# PCB_111000_CA.net
KiCad netlist of a schematic drawn in EAGLE
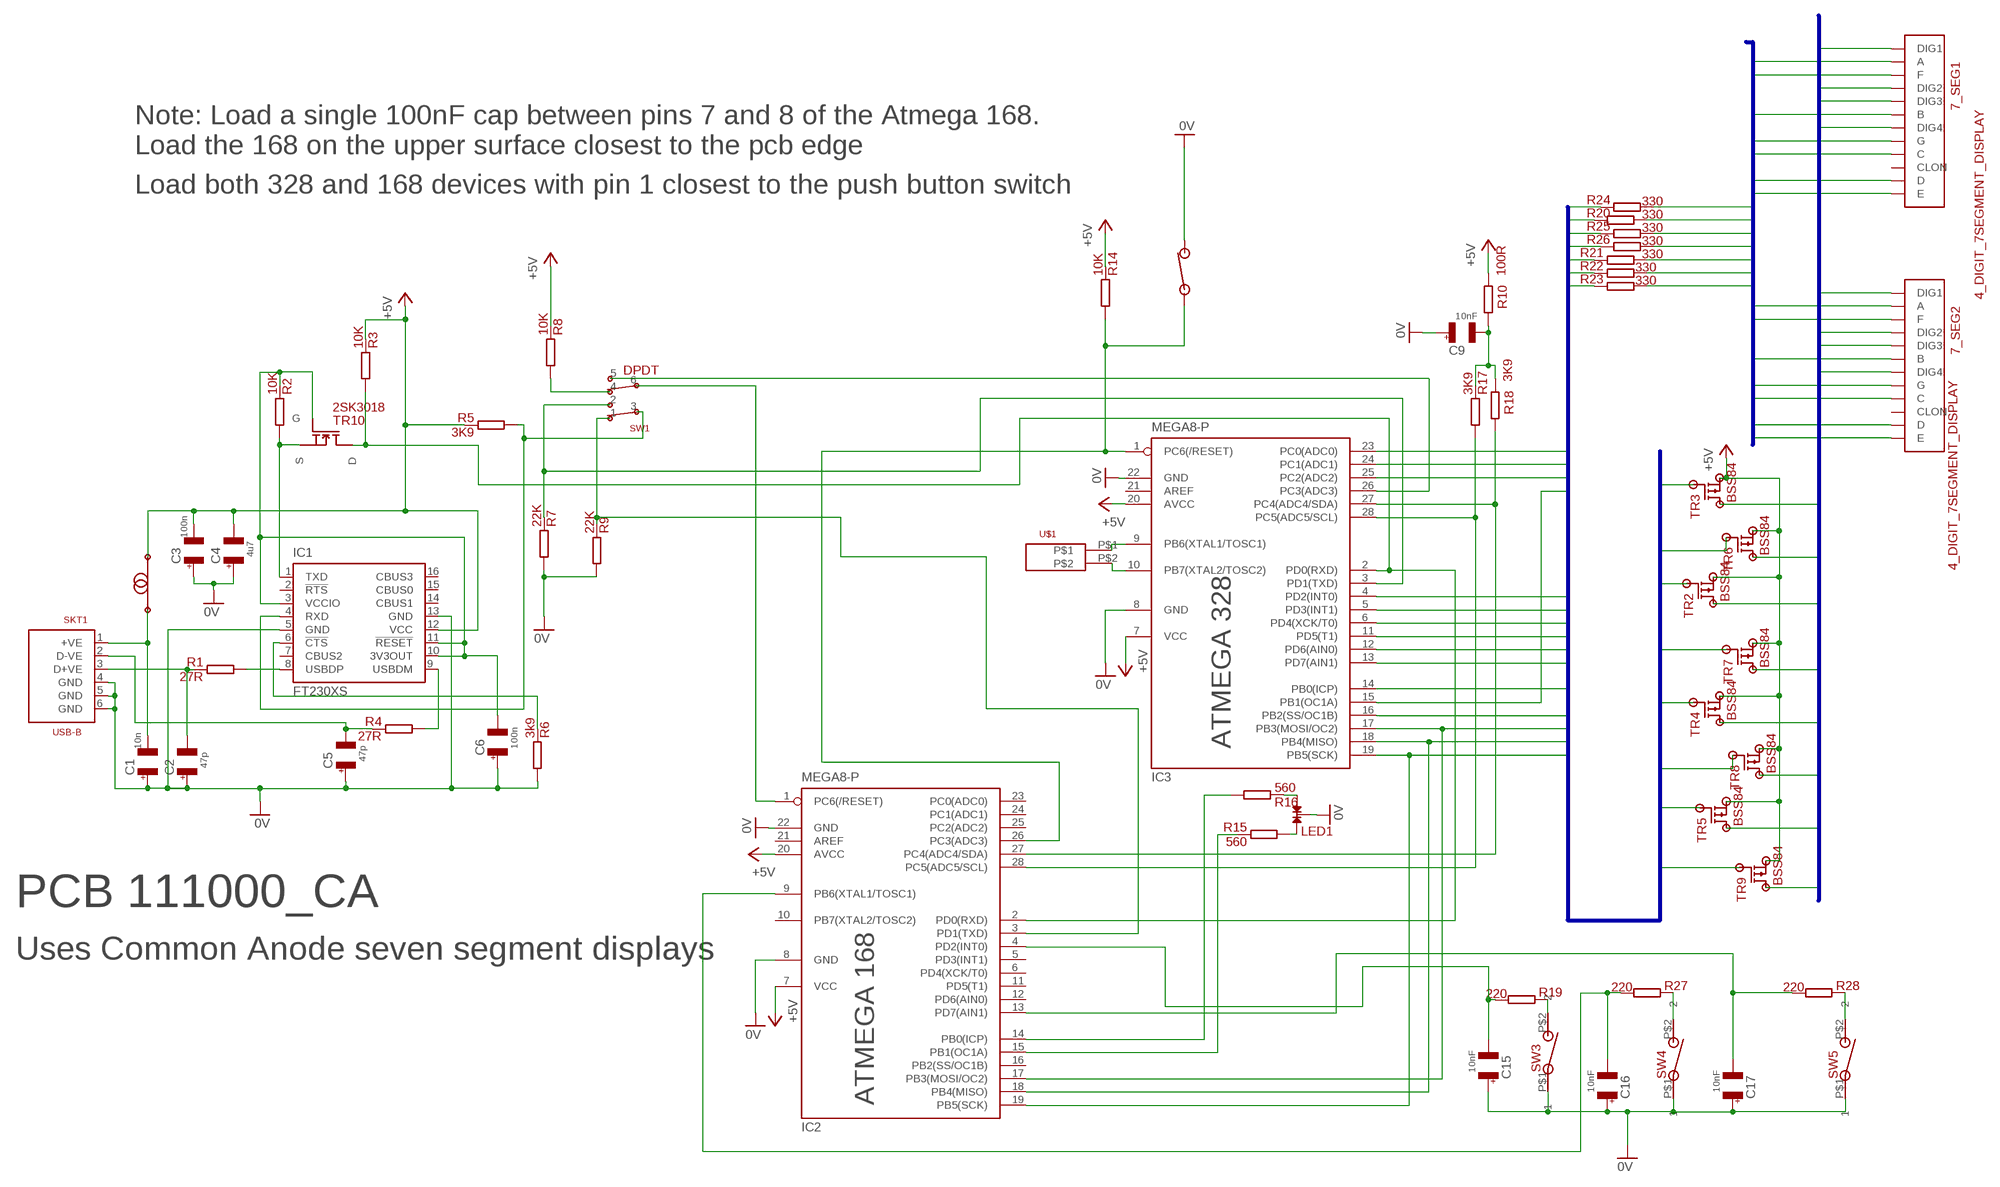
[diagram p0: schematic, sheet 1]

(export (version "E")
  (design (tool "Eeschema 10.0.6"))
  (components
    (comp (ref "7_SEG1")
      (value "4_DIGIT_7SEGMENT_DISPLAY")
      (footprint "eagle-import:4_DIGIT_7SEGMENT_DISPLAY")
      (libsource (lib "eagle-import") (part "4_DIGIT_7SEGMENT_DISPLAY"))
    )
    (comp (ref "7_SEG2")
      (value "4_DIGIT_7SEGMENT_DISPLAY")
      (footprint "eagle-import:4_DIGIT_7SEGMENT_DISPLAY")
      (libsource (lib "eagle-import") (part "4_DIGIT_7SEGMENT_DISPLAY"))
    )
    (comp (ref "C1")
      (value "10n")
      (footprint "eagle-import:1206")
      (libsource (lib "eagle-import") (part "1206C"))
    )
    (comp (ref "C2")
      (value "47p")
      (footprint "eagle-import:1206")
      (libsource (lib "eagle-import") (part "1206C"))
    )
    (comp (ref "C3")
      (value "100n")
      (footprint "eagle-import:1206")
      (libsource (lib "eagle-import") (part "1206C"))
    )
    (comp (ref "C4")
      (value "4u7")
      (footprint "eagle-import:1206")
      (libsource (lib "eagle-import") (part "1206C"))
    )
    (comp (ref "C5")
      (value "47p")
      (footprint "eagle-import:1206")
      (libsource (lib "eagle-import") (part "1206C"))
    )
    (comp (ref "C6")
      (value "100n")
      (footprint "eagle-import:1206")
      (libsource (lib "eagle-import") (part "1206C"))
    )
    (comp (ref "C9")
      (value "10nF")
      (footprint "eagle-import:1206")
      (libsource (lib "eagle-import") (part "1206C"))
    )
    (comp (ref "C15")
      (value "10nF")
      (footprint "eagle-import:1206")
      (libsource (lib "eagle-import") (part "1206C"))
    )
    (comp (ref "C16")
      (value "10nF")
      (footprint "eagle-import:1206")
      (libsource (lib "eagle-import") (part "1206C"))
    )
    (comp (ref "C17")
      (value "10nF")
      (footprint "eagle-import:1206")
      (libsource (lib "eagle-import") (part "1206C"))
    )
    (comp (ref "IC1")
      (value "FT230XS")
      (footprint "eagle-import:SSOP16")
      (libsource (lib "eagle-import") (part "FT230XS"))
    )
    (comp (ref "IC2")
      (value "MEGA8-P")
      (footprint "eagle-import:DIL28-3")
      (libsource (lib "eagle-import") (part "MEGA8-P"))
    )
    (comp (ref "IC3")
      (value "MEGA8-P")
      (footprint "eagle-import:DIL28-3")
      (libsource (lib "eagle-import") (part "MEGA8-P"))
    )
    (comp (ref "L1")
      (value "CHOKE")
      (footprint "eagle-import:1206")
      (libsource (lib "eagle-import") (part "CHOKE"))
    )
    (comp (ref "LED1")
      (value "LED")
      (footprint "eagle-import:CA_DUAL_LED")
      (libsource (lib "eagle-import") (part "LED"))
    )
    (comp (ref "R1")
      (value "27R")
      (footprint "eagle-import:1206")
      (libsource (lib "eagle-import") (part "1206R"))
    )
    (comp (ref "R2")
      (value "10K")
      (footprint "eagle-import:1206")
      (libsource (lib "eagle-import") (part "1206R"))
    )
    (comp (ref "R3")
      (value "10K")
      (footprint "eagle-import:1206")
      (libsource (lib "eagle-import") (part "1206R"))
    )
    (comp (ref "R4")
      (value "27R")
      (footprint "eagle-import:1206")
      (libsource (lib "eagle-import") (part "1206R"))
    )
    (comp (ref "R5")
      (value "3K9")
      (footprint "eagle-import:1206")
      (libsource (lib "eagle-import") (part "1206R"))
    )
    (comp (ref "R6")
      (value "3k9")
      (footprint "eagle-import:1206")
      (libsource (lib "eagle-import") (part "1206R"))
    )
    (comp (ref "R7")
      (value "22K")
      (footprint "eagle-import:1206")
      (libsource (lib "eagle-import") (part "1206R"))
    )
    (comp (ref "R8")
      (value "10K")
      (footprint "eagle-import:1206")
      (libsource (lib "eagle-import") (part "1206R"))
    )
    (comp (ref "R9")
      (value "22K")
      (footprint "eagle-import:1206")
      (libsource (lib "eagle-import") (part "1206R"))
    )
    (comp (ref "R10")
      (value "100R")
      (footprint "eagle-import:1206")
      (libsource (lib "eagle-import") (part "1206R"))
    )
    (comp (ref "R14")
      (value "10K")
      (footprint "eagle-import:1206")
      (libsource (lib "eagle-import") (part "1206R"))
    )
    (comp (ref "R15")
      (value "560")
      (footprint "eagle-import:1206")
      (libsource (lib "eagle-import") (part "1206R"))
    )
    (comp (ref "R16")
      (value "560")
      (footprint "eagle-import:1206")
      (libsource (lib "eagle-import") (part "1206R"))
    )
    (comp (ref "R17")
      (value "3K9")
      (footprint "eagle-import:1206")
      (libsource (lib "eagle-import") (part "1206R"))
    )
    (comp (ref "R18")
      (value "3K9")
      (footprint "eagle-import:1206")
      (libsource (lib "eagle-import") (part "1206R"))
    )
    (comp (ref "R19")
      (value "220")
      (footprint "eagle-import:1206")
      (libsource (lib "eagle-import") (part "1206R"))
    )
    (comp (ref "R20")
      (value "330")
      (footprint "eagle-import:1206")
      (libsource (lib "eagle-import") (part "1206R"))
    )
    (comp (ref "R21")
      (value "330")
      (footprint "eagle-import:1206")
      (libsource (lib "eagle-import") (part "1206R"))
    )
    (comp (ref "R22")
      (value "330")
      (footprint "eagle-import:1206")
      (libsource (lib "eagle-import") (part "1206R"))
    )
    (comp (ref "R23")
      (value "330")
      (footprint "eagle-import:1206")
      (libsource (lib "eagle-import") (part "1206R"))
    )
    (comp (ref "R24")
      (value "330")
      (footprint "eagle-import:1206")
      (libsource (lib "eagle-import") (part "1206R"))
    )
    (comp (ref "R25")
      (value "330")
      (footprint "eagle-import:1206")
      (libsource (lib "eagle-import") (part "1206R"))
    )
    (comp (ref "R26")
      (value "330")
      (footprint "eagle-import:1206")
      (libsource (lib "eagle-import") (part "1206R"))
    )
    (comp (ref "R27")
      (value "220")
      (footprint "eagle-import:1206")
      (libsource (lib "eagle-import") (part "1206R"))
    )
    (comp (ref "R28")
      (value "220")
      (footprint "eagle-import:1206")
      (libsource (lib "eagle-import") (part "1206R"))
    )
    (comp (ref "SKT1")
      (value "USB-B")
      (footprint "eagle-import:USB-B")
      (libsource (lib "eagle-import") (part "USB-B"))
    )
    (comp (ref "SW1")
      (value "DPDT")
      (footprint "eagle-import:DPDT_SWITCH")
      (libsource (lib "eagle-import") (part "DPDT"))
    )
    (comp (ref "SW2")
      (value "NO_SW")
      (footprint "eagle-import:SM_NO_PUSH_BUTTON")
      (libsource (lib "eagle-import") (part "NO_SW"))
    )
    (comp (ref "SW3")
      (value "NO_PB_1")
      (footprint "eagle-import:RE51-0711")
      (libsource (lib "eagle-import") (part "NO_PB_1"))
    )
    (comp (ref "SW4")
      (value "NO_PB_1")
      (footprint "eagle-import:RE51-0711")
      (libsource (lib "eagle-import") (part "NO_PB_1"))
    )
    (comp (ref "SW5")
      (value "NO_PB_1")
      (footprint "eagle-import:RE51-0711")
      (libsource (lib "eagle-import") (part "NO_PB_1"))
    )
    (comp (ref "TR2")
      (value "BSS84")
      (footprint "eagle-import:SOT23")
      (libsource (lib "eagle-import") (part "BSS84"))
    )
    (comp (ref "TR3")
      (value "BSS84")
      (footprint "eagle-import:SOT23")
      (libsource (lib "eagle-import") (part "BSS84"))
    )
    (comp (ref "TR4")
      (value "BSS84")
      (footprint "eagle-import:SOT23")
      (libsource (lib "eagle-import") (part "BSS84"))
    )
    (comp (ref "TR5")
      (value "BSS84")
      (footprint "eagle-import:SOT23")
      (libsource (lib "eagle-import") (part "BSS84"))
    )
    (comp (ref "TR6")
      (value "BSS84")
      (footprint "eagle-import:SOT23")
      (libsource (lib "eagle-import") (part "BSS84"))
    )
    (comp (ref "TR7")
      (value "BSS84")
      (footprint "eagle-import:SOT23")
      (libsource (lib "eagle-import") (part "BSS84"))
    )
    (comp (ref "TR8")
      (value "BSS84")
      (footprint "eagle-import:SOT23")
      (libsource (lib "eagle-import") (part "BSS84"))
    )
    (comp (ref "TR9")
      (value "BSS84")
      (footprint "eagle-import:SOT23")
      (libsource (lib "eagle-import") (part "BSS84"))
    )
    (comp (ref "TR10")
      (value "2SK3018")
      (footprint "eagle-import:2SK3018")
      (libsource (lib "eagle-import") (part "2SK3018"))
    )
    (comp (ref "U$1")
      (value "XTAL")
      (footprint "eagle-import:XTAL_VIAS")
      (libsource (lib "eagle-import") (part "XTAL"))
    )
  )
  (nets
    (net (code "1") (name "+5V") (class "Default")
      (node (ref "C3") (pin "P$2") (pinfunction "2_P$2") (pintype "bidirectional"))
      (node (ref "C4") (pin "P$2") (pinfunction "2_P$2") (pintype "bidirectional"))
      (node (ref "IC1") (pin "12") (pinfunction "VCC_12") (pintype "power_in"))
      (node (ref "IC2") (pin "20") (pinfunction "AVCC_20") (pintype "power_in"))
      (node (ref "IC2") (pin "7") (pinfunction "VCC_7") (pintype "power_in"))
      (node (ref "IC3") (pin "20") (pinfunction "AVCC_20") (pintype "power_in"))
      (node (ref "IC3") (pin "7") (pinfunction "VCC_7") (pintype "power_in"))
      (node (ref "L1") (pin "P$2") (pinfunction "2_P$2") (pintype "bidirectional"))
      (node (ref "R10") (pin "P$2") (pinfunction "P$2_P$2") (pintype "bidirectional"))
      (node (ref "R14") (pin "P$2") (pinfunction "P$2_P$2") (pintype "bidirectional"))
      (node (ref "R3") (pin "P$2") (pinfunction "P$2_P$2") (pintype "bidirectional"))
      (node (ref "R5") (pin "P$2") (pinfunction "P$2_P$2") (pintype "bidirectional"))
      (node (ref "R8") (pin "P$2") (pinfunction "P$2_P$2") (pintype "bidirectional"))
      (node (ref "TR2") (pin "2") (pinfunction "S_2") (pintype "bidirectional"))
      (node (ref "TR3") (pin "2") (pinfunction "S_2") (pintype "bidirectional"))
      (node (ref "TR4") (pin "2") (pinfunction "S_2") (pintype "bidirectional"))
      (node (ref "TR5") (pin "2") (pinfunction "S_2") (pintype "bidirectional"))
      (node (ref "TR6") (pin "2") (pinfunction "S_2") (pintype "bidirectional"))
      (node (ref "TR7") (pin "2") (pinfunction "S_2") (pintype "bidirectional"))
      (node (ref "TR8") (pin "2") (pinfunction "S_2") (pintype "bidirectional"))
      (node (ref "TR9") (pin "2") (pinfunction "S_2") (pintype "bidirectional"))
    )
    (net (code "2") (name "/DIGIT0") (class "Default")
      (node (ref "7_SEG1") (pin "P$12") (pinfunction "DIG1_P$12") (pintype "bidirectional"))
      (node (ref "TR4") (pin "3") (pinfunction "D_3") (pintype "bidirectional"))
    )
    (net (code "3") (name "/DIGIT1") (class "Default")
      (node (ref "7_SEG1") (pin "P$9") (pinfunction "DIG2_P$9") (pintype "bidirectional"))
      (node (ref "TR8") (pin "3") (pinfunction "D_3") (pintype "bidirectional"))
    )
    (net (code "4") (name "/DIGIT2") (class "Default")
      (node (ref "7_SEG1") (pin "P$8") (pinfunction "DIG3_P$8") (pintype "bidirectional"))
      (node (ref "TR5") (pin "3") (pinfunction "D_3") (pintype "bidirectional"))
    )
    (net (code "5") (name "/DIGIT3") (class "Default")
      (node (ref "7_SEG1") (pin "P$6") (pinfunction "DIG4_P$6") (pintype "bidirectional"))
      (node (ref "TR9") (pin "3") (pinfunction "D_3") (pintype "bidirectional"))
    )
    (net (code "6") (name "/DIGIT4") (class "Default")
      (node (ref "7_SEG2") (pin "P$12") (pinfunction "DIG1_P$12") (pintype "bidirectional"))
      (node (ref "TR3") (pin "3") (pinfunction "D_3") (pintype "bidirectional"))
    )
    (net (code "7") (name "/DIGIT5") (class "Default")
      (node (ref "7_SEG2") (pin "P$9") (pinfunction "DIG2_P$9") (pintype "bidirectional"))
      (node (ref "TR6") (pin "3") (pinfunction "D_3") (pintype "bidirectional"))
    )
    (net (code "8") (name "/DIGIT6") (class "Default")
      (node (ref "7_SEG2") (pin "P$8") (pinfunction "DIG3_P$8") (pintype "bidirectional"))
      (node (ref "TR2") (pin "3") (pinfunction "D_3") (pintype "bidirectional"))
    )
    (net (code "9") (name "/DIGIT7") (class "Default")
      (node (ref "7_SEG2") (pin "P$6") (pinfunction "DIG4_P$6") (pintype "bidirectional"))
      (node (ref "TR7") (pin "3") (pinfunction "D_3") (pintype "bidirectional"))
    )
    (net (code "10") (name "/DISPLAY_DRIVER0") (class "Default")
      (node (ref "IC3") (pin "15") (pinfunction "PB1(OC1A)_15") (pintype "bidirectional"))
      (node (ref "R24") (pin "P$2") (pinfunction "P$2_P$2") (pintype "bidirectional"))
    )
    (net (code "11") (name "/DISPLAY_DRIVER1") (class "Default")
      (node (ref "IC3") (pin "4") (pinfunction "PD2(INT0)_4") (pintype "bidirectional"))
      (node (ref "R20") (pin "P$2") (pinfunction "P$2_P$2") (pintype "bidirectional"))
    )
    (net (code "12") (name "/DISPLAY_DRIVER2") (class "Default")
      (node (ref "IC3") (pin "5") (pinfunction "PD3(INT1)_5") (pintype "bidirectional"))
      (node (ref "R25") (pin "P$2") (pinfunction "P$2_P$2") (pintype "bidirectional"))
    )
    (net (code "13") (name "/DISPLAY_DRIVER3") (class "Default")
      (node (ref "IC3") (pin "6") (pinfunction "PD4(XCK/T0)_6") (pintype "bidirectional"))
      (node (ref "R26") (pin "P$2") (pinfunction "P$2_P$2") (pintype "bidirectional"))
    )
    (net (code "14") (name "/DISPLAY_DRIVER4") (class "Default")
      (node (ref "IC3") (pin "11") (pinfunction "PD5(T1)_11") (pintype "bidirectional"))
      (node (ref "R21") (pin "P$2") (pinfunction "P$2_P$2") (pintype "bidirectional"))
    )
    (net (code "15") (name "/DISPLAY_DRIVER5") (class "Default")
      (node (ref "IC3") (pin "12") (pinfunction "PD6(AIN0)_12") (pintype "bidirectional"))
      (node (ref "R22") (pin "P$2") (pinfunction "P$2_P$2") (pintype "bidirectional"))
    )
    (net (code "16") (name "/DISPLAY_DRIVER6") (class "Default")
      (node (ref "IC3") (pin "13") (pinfunction "PD7(AIN1)_13") (pintype "bidirectional"))
      (node (ref "R23") (pin "P$2") (pinfunction "P$2_P$2") (pintype "bidirectional"))
    )
    (net (code "17") (name "/DISPLAY_DRIVER8") (class "Default")
      (node (ref "IC3") (pin "14") (pinfunction "PB0(ICP)_14") (pintype "bidirectional"))
      (node (ref "TR3") (pin "1") (pinfunction "G_1") (pintype "bidirectional"))
    )
    (net (code "18") (name "/DISPLAY_DRIVER9") (class "Default")
      (node (ref "IC3") (pin "16") (pinfunction "PB2(SS/OC1B)_16") (pintype "bidirectional"))
      (node (ref "TR6") (pin "1") (pinfunction "G_1") (pintype "bidirectional"))
    )
    (net (code "19") (name "/DISPLAY_DRIVER10") (class "Default")
      (node (ref "IC2") (pin "17") (pinfunction "PB3(MOSI/OC2)_17") (pintype "bidirectional"))
      (node (ref "IC3") (pin "17") (pinfunction "PB3(MOSI/OC2)_17") (pintype "bidirectional"))
      (node (ref "TR2") (pin "1") (pinfunction "G_1") (pintype "bidirectional"))
    )
    (net (code "20") (name "/DISPLAY_DRIVER11") (class "Default")
      (node (ref "IC2") (pin "18") (pinfunction "PB4(MISO)_18") (pintype "bidirectional"))
      (node (ref "IC3") (pin "18") (pinfunction "PB4(MISO)_18") (pintype "bidirectional"))
      (node (ref "TR7") (pin "1") (pinfunction "G_1") (pintype "bidirectional"))
    )
    (net (code "21") (name "/DISPLAY_DRIVER12") (class "Default")
      (node (ref "IC2") (pin "19") (pinfunction "PB5(SCK)_19") (pintype "bidirectional"))
      (node (ref "IC3") (pin "19") (pinfunction "PB5(SCK)_19") (pintype "bidirectional"))
      (node (ref "TR4") (pin "1") (pinfunction "G_1") (pintype "bidirectional"))
    )
    (net (code "22") (name "/DISPLAY_DRIVER13") (class "Default")
      (node (ref "IC3") (pin "23") (pinfunction "PC0(ADC0)_23") (pintype "bidirectional"))
      (node (ref "TR8") (pin "1") (pinfunction "G_1") (pintype "bidirectional"))
    )
    (net (code "23") (name "/DISPLAY_DRIVER14") (class "Default")
      (node (ref "IC3") (pin "24") (pinfunction "PC1(ADC1)_24") (pintype "bidirectional"))
      (node (ref "TR5") (pin "1") (pinfunction "G_1") (pintype "bidirectional"))
    )
    (net (code "24") (name "/DISPLAY_DRIVER15") (class "Default")
      (node (ref "IC3") (pin "25") (pinfunction "PC2(ADC2)_25") (pintype "bidirectional"))
      (node (ref "TR9") (pin "1") (pinfunction "G_1") (pintype "bidirectional"))
    )
    (net (code "25") (name "/SEVEN_SEG0") (class "Default")
      (node (ref "7_SEG1") (pin "P$11") (pinfunction "A_P$11") (pintype "bidirectional"))
      (node (ref "7_SEG2") (pin "P$11") (pinfunction "A_P$11") (pintype "bidirectional"))
      (node (ref "R24") (pin "P$1") (pinfunction "P$1_P$1") (pintype "bidirectional"))
    )
    (net (code "26") (name "/SEVEN_SEG1") (class "Default")
      (node (ref "7_SEG1") (pin "P$7") (pinfunction "B_P$7") (pintype "bidirectional"))
      (node (ref "7_SEG2") (pin "P$7") (pinfunction "B_P$7") (pintype "bidirectional"))
      (node (ref "R20") (pin "P$1") (pinfunction "P$1_P$1") (pintype "bidirectional"))
    )
    (net (code "27") (name "/SEVEN_SEG2") (class "Default")
      (node (ref "7_SEG1") (pin "P$4") (pinfunction "C_P$4") (pintype "bidirectional"))
      (node (ref "7_SEG2") (pin "P$4") (pinfunction "C_P$4") (pintype "bidirectional"))
      (node (ref "R25") (pin "P$1") (pinfunction "P$1_P$1") (pintype "bidirectional"))
    )
    (net (code "28") (name "/SEVEN_SEG3") (class "Default")
      (node (ref "7_SEG1") (pin "P$2") (pinfunction "D_P$2") (pintype "bidirectional"))
      (node (ref "7_SEG2") (pin "P$2") (pinfunction "D_P$2") (pintype "bidirectional"))
      (node (ref "R26") (pin "P$1") (pinfunction "P$1_P$1") (pintype "bidirectional"))
    )
    (net (code "29") (name "/SEVEN_SEG4") (class "Default")
      (node (ref "7_SEG1") (pin "P$1") (pinfunction "E_P$1") (pintype "bidirectional"))
      (node (ref "7_SEG2") (pin "P$1") (pinfunction "E_P$1") (pintype "bidirectional"))
      (node (ref "R21") (pin "P$1") (pinfunction "P$1_P$1") (pintype "bidirectional"))
    )
    (net (code "30") (name "/SEVEN_SEG5") (class "Default")
      (node (ref "7_SEG1") (pin "P$10") (pinfunction "F_P$10") (pintype "bidirectional"))
      (node (ref "7_SEG2") (pin "P$10") (pinfunction "F_P$10") (pintype "bidirectional"))
      (node (ref "R22") (pin "P$1") (pinfunction "P$1_P$1") (pintype "bidirectional"))
    )
    (net (code "31") (name "/SEVEN_SEG6") (class "Default")
      (node (ref "7_SEG1") (pin "P$5") (pinfunction "G_P$5") (pintype "bidirectional"))
      (node (ref "7_SEG2") (pin "P$5") (pinfunction "G_P$5") (pintype "bidirectional"))
      (node (ref "R23") (pin "P$1") (pinfunction "P$1_P$1") (pintype "bidirectional"))
    )
    (net (code "32") (name "0V") (class "Default")
      (node (ref "C1") (pin "P$1") (pinfunction "1_P$1") (pintype "bidirectional"))
      (node (ref "C15") (pin "P$1") (pinfunction "1_P$1") (pintype "bidirectional"))
      (node (ref "C16") (pin "P$1") (pinfunction "1_P$1") (pintype "bidirectional"))
      (node (ref "C17") (pin "P$1") (pinfunction "1_P$1") (pintype "bidirectional"))
      (node (ref "C2") (pin "P$1") (pinfunction "1_P$1") (pintype "bidirectional"))
      (node (ref "C3") (pin "P$1") (pinfunction "1_P$1") (pintype "bidirectional"))
      (node (ref "C4") (pin "P$1") (pinfunction "1_P$1") (pintype "bidirectional"))
      (node (ref "C5") (pin "P$1") (pinfunction "1_P$1") (pintype "bidirectional"))
      (node (ref "C6") (pin "P$1") (pinfunction "1_P$1") (pintype "bidirectional"))
      (node (ref "C9") (pin "P$1") (pinfunction "1_P$1") (pintype "bidirectional"))
      (node (ref "IC1") (pin "13") (pinfunction "GND_13") (pintype "power_in"))
      (node (ref "IC1") (pin "5") (pinfunction "GND_5") (pintype "power_in"))
      (node (ref "IC2") (pin "22") (pinfunction "GND_22") (pintype "power_in"))
      (node (ref "IC2") (pin "8") (pinfunction "GND_8") (pintype "power_in"))
      (node (ref "IC3") (pin "22") (pinfunction "GND_22") (pintype "power_in"))
      (node (ref "IC3") (pin "8") (pinfunction "GND_8") (pintype "power_in"))
      (node (ref "LED1") (pin "2") (pinfunction "2_2") (pintype "bidirectional"))
      (node (ref "R6") (pin "P$1") (pinfunction "P$1_P$1") (pintype "bidirectional"))
      (node (ref "R7") (pin "P$1") (pinfunction "P$1_P$1") (pintype "bidirectional"))
      (node (ref "R9") (pin "P$1") (pinfunction "P$1_P$1") (pintype "bidirectional"))
      (node (ref "SKT1") (pin "4") (pinfunction "GND_4") (pintype "bidirectional"))
      (node (ref "SKT1") (pin "5") (pinfunction "GND_5") (pintype "bidirectional"))
      (node (ref "SKT1") (pin "6") (pinfunction "GND_6") (pintype "bidirectional"))
      (node (ref "SW2") (pin "P$2") (pinfunction "2_P$2") (pintype "bidirectional"))
      (node (ref "SW3") (pin "P$1") (pinfunction "1_P$1") (pintype "bidirectional"))
      (node (ref "SW4") (pin "P$1") (pinfunction "1_P$1") (pintype "bidirectional"))
      (node (ref "SW5") (pin "P$1") (pinfunction "1_P$1") (pintype "bidirectional"))
    )
    (net (code "33") (name "Net-(C1-2)") (class "Default")
      (node (ref "C1") (pin "P$2") (pinfunction "2_P$2") (pintype "bidirectional"))
      (node (ref "L1") (pin "P$1") (pinfunction "1_P$1") (pintype "bidirectional"))
      (node (ref "SKT1") (pin "1") (pinfunction "+VE_1") (pintype "bidirectional"))
    )
    (net (code "34") (name "Net-(C2-2)") (class "Default")
      (node (ref "C2") (pin "P$2") (pinfunction "2_P$2") (pintype "bidirectional"))
      (node (ref "R1") (pin "P$2") (pinfunction "P$2_P$2") (pintype "bidirectional"))
      (node (ref "SKT1") (pin "3") (pinfunction "D+VE_3") (pintype "bidirectional"))
    )
    (net (code "35") (name "Net-(C5-2)") (class "Default")
      (node (ref "C5") (pin "P$2") (pinfunction "2_P$2") (pintype "bidirectional"))
      (node (ref "R4") (pin "P$2") (pinfunction "P$2_P$2") (pintype "bidirectional"))
      (node (ref "SKT1") (pin "2") (pinfunction "D-VE_2") (pintype "bidirectional"))
    )
    (net (code "36") (name "Net-(C6-2)") (class "Default")
      (node (ref "C6") (pin "P$2") (pinfunction "2_P$2") (pintype "bidirectional"))
      (node (ref "IC1") (pin "10") (pinfunction "3V3OUT_10") (pintype "output"))
      (node (ref "IC1") (pin "11") (pinfunction "~{RESET}_11") (pintype "input"))
      (node (ref "IC1") (pin "3") (pinfunction "VCCIO_3") (pintype "power_in"))
      (node (ref "R2") (pin "P$2") (pinfunction "P$2_P$2") (pintype "bidirectional"))
      (node (ref "TR10") (pin "2") (pinfunction "G_2") (pintype "bidirectional"))
    )
    (net (code "37") (name "Net-(C9-2)") (class "Default")
      (node (ref "C9") (pin "P$2") (pinfunction "2_P$2") (pintype "bidirectional"))
      (node (ref "R10") (pin "P$1") (pinfunction "P$1_P$1") (pintype "bidirectional"))
      (node (ref "R17") (pin "P$2") (pinfunction "P$2_P$2") (pintype "bidirectional"))
      (node (ref "R18") (pin "P$2") (pinfunction "P$2_P$2") (pintype "bidirectional"))
    )
    (net (code "38") (name "Net-(C15-2)") (class "Default")
      (node (ref "C15") (pin "P$2") (pinfunction "2_P$2") (pintype "bidirectional"))
      (node (ref "IC2") (pin "4") (pinfunction "PD2(INT0)_4") (pintype "bidirectional"))
      (node (ref "R19") (pin "P$1") (pinfunction "P$1_P$1") (pintype "bidirectional"))
    )
    (net (code "39") (name "Net-(C16-2)") (class "Default")
      (node (ref "C16") (pin "P$2") (pinfunction "2_P$2") (pintype "bidirectional"))
      (node (ref "IC2") (pin "9") (pinfunction "PB6(XTAL1/TOSC1)_9") (pintype "bidirectional"))
      (node (ref "R27") (pin "P$1") (pinfunction "P$1_P$1") (pintype "bidirectional"))
    )
    (net (code "40") (name "Net-(C17-2)") (class "Default")
      (node (ref "C17") (pin "P$2") (pinfunction "2_P$2") (pintype "bidirectional"))
      (node (ref "IC2") (pin "13") (pinfunction "PD7(AIN1)_13") (pintype "bidirectional"))
      (node (ref "R28") (pin "P$1") (pinfunction "P$1_P$1") (pintype "bidirectional"))
    )
    (net (code "41") (name "Net-(IC1-RXD)") (class "Default")
      (node (ref "IC1") (pin "4") (pinfunction "RXD_4") (pintype "input"))
      (node (ref "R5") (pin "P$1") (pinfunction "P$1_P$1") (pintype "bidirectional"))
      (node (ref "SW1") (pin "3") (pinfunction "3_3") (pintype "bidirectional"))
    )
    (net (code "42") (name "Net-(IC1-TXD)") (class "Default")
      (node (ref "IC1") (pin "1") (pinfunction "TXD_1") (pintype "output"))
      (node (ref "R2") (pin "P$1") (pinfunction "P$1_P$1") (pintype "bidirectional"))
      (node (ref "TR10") (pin "1") (pinfunction "S_1") (pintype "bidirectional"))
    )
    (net (code "43") (name "Net-(IC1-USBDM)") (class "Default")
      (node (ref "IC1") (pin "9") (pinfunction "USBDM_9") (pintype "input"))
      (node (ref "R4") (pin "P$1") (pinfunction "P$1_P$1") (pintype "bidirectional"))
    )
    (net (code "44") (name "Net-(IC1-USBDP)") (class "Default")
      (node (ref "IC1") (pin "8") (pinfunction "USBDP_8") (pintype "input"))
      (node (ref "R1") (pin "P$1") (pinfunction "P$1_P$1") (pintype "bidirectional"))
    )
    (net (code "45") (name "Net-(IC1-~{CTS})") (class "Default")
      (node (ref "IC1") (pin "6") (pinfunction "~{CTS}_6") (pintype "input"))
      (node (ref "R6") (pin "P$2") (pinfunction "P$2_P$2") (pintype "bidirectional"))
    )
    (net (code "46") (name "Net-(IC2-PB0(ICP))") (class "Default")
      (node (ref "IC2") (pin "14") (pinfunction "PB0(ICP)_14") (pintype "bidirectional"))
      (node (ref "R16") (pin "P$1") (pinfunction "P$1_P$1") (pintype "bidirectional"))
    )
    (net (code "47") (name "Net-(IC2-PB1(OC1A))") (class "Default")
      (node (ref "IC2") (pin "15") (pinfunction "PB1(OC1A)_15") (pintype "bidirectional"))
      (node (ref "R15") (pin "P$2") (pinfunction "P$2_P$2") (pintype "bidirectional"))
    )
    (net (code "48") (name "Net-(IC2-PC3(ADC3))") (class "Default")
      (node (ref "IC2") (pin "26") (pinfunction "PC3(ADC3)_26") (pintype "bidirectional"))
      (node (ref "IC3") (pin "1") (pinfunction "PC6(/RESET)_1") (pintype "bidirectional"))
      (node (ref "R14") (pin "P$1") (pinfunction "P$1_P$1") (pintype "bidirectional"))
      (node (ref "SW2") (pin "P$1") (pinfunction "1_P$1") (pintype "bidirectional"))
    )
    (net (code "49") (name "Net-(IC2-PC4(ADC4{slash}SDA))") (class "Default")
      (node (ref "IC2") (pin "27") (pinfunction "PC4(ADC4/SDA)_27") (pintype "bidirectional"))
      (node (ref "IC3") (pin "27") (pinfunction "PC4(ADC4/SDA)_27") (pintype "bidirectional"))
      (node (ref "R18") (pin "P$1") (pinfunction "P$1_P$1") (pintype "bidirectional"))
    )
    (net (code "50") (name "Net-(IC2-PC5(ADC5{slash}SCL))") (class "Default")
      (node (ref "IC2") (pin "28") (pinfunction "PC5(ADC5/SCL)_28") (pintype "bidirectional"))
      (node (ref "IC3") (pin "28") (pinfunction "PC5(ADC5/SCL)_28") (pintype "bidirectional"))
      (node (ref "R17") (pin "P$1") (pinfunction "P$1_P$1") (pintype "bidirectional"))
    )
    (net (code "51") (name "Net-(IC2-PC6({slash}RESET))") (class "Default")
      (node (ref "IC2") (pin "1") (pinfunction "PC6(/RESET)_1") (pintype "bidirectional"))
      (node (ref "SW1") (pin "6") (pinfunction "6_6") (pintype "bidirectional"))
    )
    (net (code "52") (name "Net-(IC2-PD0(RXD))") (class "Default")
      (node (ref "IC2") (pin "2") (pinfunction "PD0(RXD)_2") (pintype "bidirectional"))
      (node (ref "IC3") (pin "2") (pinfunction "PD0(RXD)_2") (pintype "bidirectional"))
      (node (ref "R3") (pin "P$1") (pinfunction "P$1_P$1") (pintype "bidirectional"))
      (node (ref "TR10") (pin "3") (pinfunction "D_3") (pintype "bidirectional"))
    )
    (net (code "53") (name "Net-(IC2-PD1(TXD))") (class "Default")
      (node (ref "IC2") (pin "3") (pinfunction "PD1(TXD)_3") (pintype "bidirectional"))
      (node (ref "R9") (pin "P$2") (pinfunction "P$2_P$2") (pintype "bidirectional"))
      (node (ref "SW1") (pin "1") (pinfunction "1_1") (pintype "bidirectional"))
    )
    (net (code "54") (name "Net-(IC3-PB6(XTAL1{slash}TOSC1))") (class "Default")
      (node (ref "IC3") (pin "9") (pinfunction "PB6(XTAL1/TOSC1)_9") (pintype "bidirectional"))
      (node (ref "U$1") (pin "P$1") (pinfunction "P$1_P$1") (pintype "bidirectional"))
    )
    (net (code "55") (name "Net-(IC3-PB7(XTAL2{slash}TOSC2))") (class "Default")
      (node (ref "IC3") (pin "10") (pinfunction "PB7(XTAL2/TOSC2)_10") (pintype "bidirectional"))
      (node (ref "U$1") (pin "P$2") (pinfunction "P$2_P$2") (pintype "bidirectional"))
    )
    (net (code "56") (name "Net-(IC3-PC3(ADC3))") (class "Default")
      (node (ref "IC3") (pin "26") (pinfunction "PC3(ADC3)_26") (pintype "bidirectional"))
      (node (ref "SW1") (pin "5") (pinfunction "5_5") (pintype "bidirectional"))
    )
    (net (code "57") (name "Net-(IC3-PD1(TXD))") (class "Default")
      (node (ref "IC3") (pin "3") (pinfunction "PD1(TXD)_3") (pintype "bidirectional"))
      (node (ref "R7") (pin "P$2") (pinfunction "P$2_P$2") (pintype "bidirectional"))
      (node (ref "SW1") (pin "2") (pinfunction "2_2") (pintype "bidirectional"))
    )
    (net (code "58") (name "Net-(LED1-Pad1)") (class "Default")
      (node (ref "LED1") (pin "1") (pinfunction "1_1") (pintype "bidirectional"))
      (node (ref "R15") (pin "P$1") (pinfunction "P$1_P$1") (pintype "bidirectional"))
    )
    (net (code "59") (name "Net-(LED1-Pad3)") (class "Default")
      (node (ref "LED1") (pin "3") (pinfunction "3_3") (pintype "bidirectional"))
      (node (ref "R16") (pin "P$2") (pinfunction "P$2_P$2") (pintype "bidirectional"))
    )
    (net (code "60") (name "Net-(R8-PadP$1)") (class "Default")
      (node (ref "R8") (pin "P$1") (pinfunction "P$1_P$1") (pintype "bidirectional"))
      (node (ref "SW1") (pin "4") (pinfunction "4_4") (pintype "bidirectional"))
    )
    (net (code "61") (name "Net-(SW3-2)") (class "Default")
      (node (ref "R19") (pin "P$2") (pinfunction "P$2_P$2") (pintype "bidirectional"))
      (node (ref "SW3") (pin "P$2") (pinfunction "2_P$2") (pintype "bidirectional"))
    )
    (net (code "62") (name "Net-(SW4-2)") (class "Default")
      (node (ref "R27") (pin "P$2") (pinfunction "P$2_P$2") (pintype "bidirectional"))
      (node (ref "SW4") (pin "P$2") (pinfunction "2_P$2") (pintype "bidirectional"))
    )
    (net (code "63") (name "Net-(SW5-2)") (class "Default")
      (node (ref "R28") (pin "P$2") (pinfunction "P$2_P$2") (pintype "bidirectional"))
      (node (ref "SW5") (pin "P$2") (pinfunction "2_P$2") (pintype "bidirectional"))
    )
    (net (code "64") (name "unconnected-(7_SEG1-CLON-PadP$3)") (class "Default")
      (node (ref "7_SEG1") (pin "P$3") (pinfunction "CLON_P$3") (pintype "bidirectional"))
    )
    (net (code "65") (name "unconnected-(7_SEG2-CLON-PadP$3)") (class "Default")
      (node (ref "7_SEG2") (pin "P$3") (pinfunction "CLON_P$3") (pintype "bidirectional"))
    )
    (net (code "66") (name "unconnected-(IC1-CBUS0-Pad15)") (class "Default")
      (node (ref "IC1") (pin "15") (pinfunction "CBUS0_15") (pintype "bidirectional"))
    )
    (net (code "67") (name "unconnected-(IC1-CBUS1-Pad14)") (class "Default")
      (node (ref "IC1") (pin "14") (pinfunction "CBUS1_14") (pintype "bidirectional"))
    )
    (net (code "68") (name "unconnected-(IC1-CBUS2-Pad7)") (class "Default")
      (node (ref "IC1") (pin "7") (pinfunction "CBUS2_7") (pintype "bidirectional"))
    )
    (net (code "69") (name "unconnected-(IC1-CBUS3-Pad16)") (class "Default")
      (node (ref "IC1") (pin "16") (pinfunction "CBUS3_16") (pintype "bidirectional"))
    )
    (net (code "70") (name "unconnected-(IC1-~{RTS}-Pad2)") (class "Default")
      (node (ref "IC1") (pin "2") (pinfunction "~{RTS}_2") (pintype "output"))
    )
    (net (code "71") (name "unconnected-(IC2-AREF-Pad21)") (class "Default")
      (node (ref "IC2") (pin "21") (pinfunction "AREF_21") (pintype "passive"))
    )
    (net (code "72") (name "unconnected-(IC2-PB2(SS{slash}OC1B)-Pad16)") (class "Default")
      (node (ref "IC2") (pin "16") (pinfunction "PB2(SS/OC1B)_16") (pintype "bidirectional"))
    )
    (net (code "73") (name "unconnected-(IC2-PB7(XTAL2{slash}TOSC2)-Pad10)") (class "Default")
      (node (ref "IC2") (pin "10") (pinfunction "PB7(XTAL2/TOSC2)_10") (pintype "bidirectional"))
    )
    (net (code "74") (name "unconnected-(IC2-PC0(ADC0)-Pad23)") (class "Default")
      (node (ref "IC2") (pin "23") (pinfunction "PC0(ADC0)_23") (pintype "bidirectional"))
    )
    (net (code "75") (name "unconnected-(IC2-PC1(ADC1)-Pad24)") (class "Default")
      (node (ref "IC2") (pin "24") (pinfunction "PC1(ADC1)_24") (pintype "bidirectional"))
    )
    (net (code "76") (name "unconnected-(IC2-PC2(ADC2)-Pad25)") (class "Default")
      (node (ref "IC2") (pin "25") (pinfunction "PC2(ADC2)_25") (pintype "bidirectional"))
    )
    (net (code "77") (name "unconnected-(IC2-PD3(INT1)-Pad5)") (class "Default")
      (node (ref "IC2") (pin "5") (pinfunction "PD3(INT1)_5") (pintype "bidirectional"))
    )
    (net (code "78") (name "unconnected-(IC2-PD4(XCK{slash}T0)-Pad6)") (class "Default")
      (node (ref "IC2") (pin "6") (pinfunction "PD4(XCK/T0)_6") (pintype "bidirectional"))
    )
    (net (code "79") (name "unconnected-(IC2-PD5(T1)-Pad11)") (class "Default")
      (node (ref "IC2") (pin "11") (pinfunction "PD5(T1)_11") (pintype "bidirectional"))
    )
    (net (code "80") (name "unconnected-(IC2-PD6(AIN0)-Pad12)") (class "Default")
      (node (ref "IC2") (pin "12") (pinfunction "PD6(AIN0)_12") (pintype "bidirectional"))
    )
    (net (code "81") (name "unconnected-(IC3-AREF-Pad21)") (class "Default")
      (node (ref "IC3") (pin "21") (pinfunction "AREF_21") (pintype "passive"))
    )
  )
)
